# 07_-_CPU_CONNECTORS.net
KiCad netlist of a schematic drawn in Altium Designer
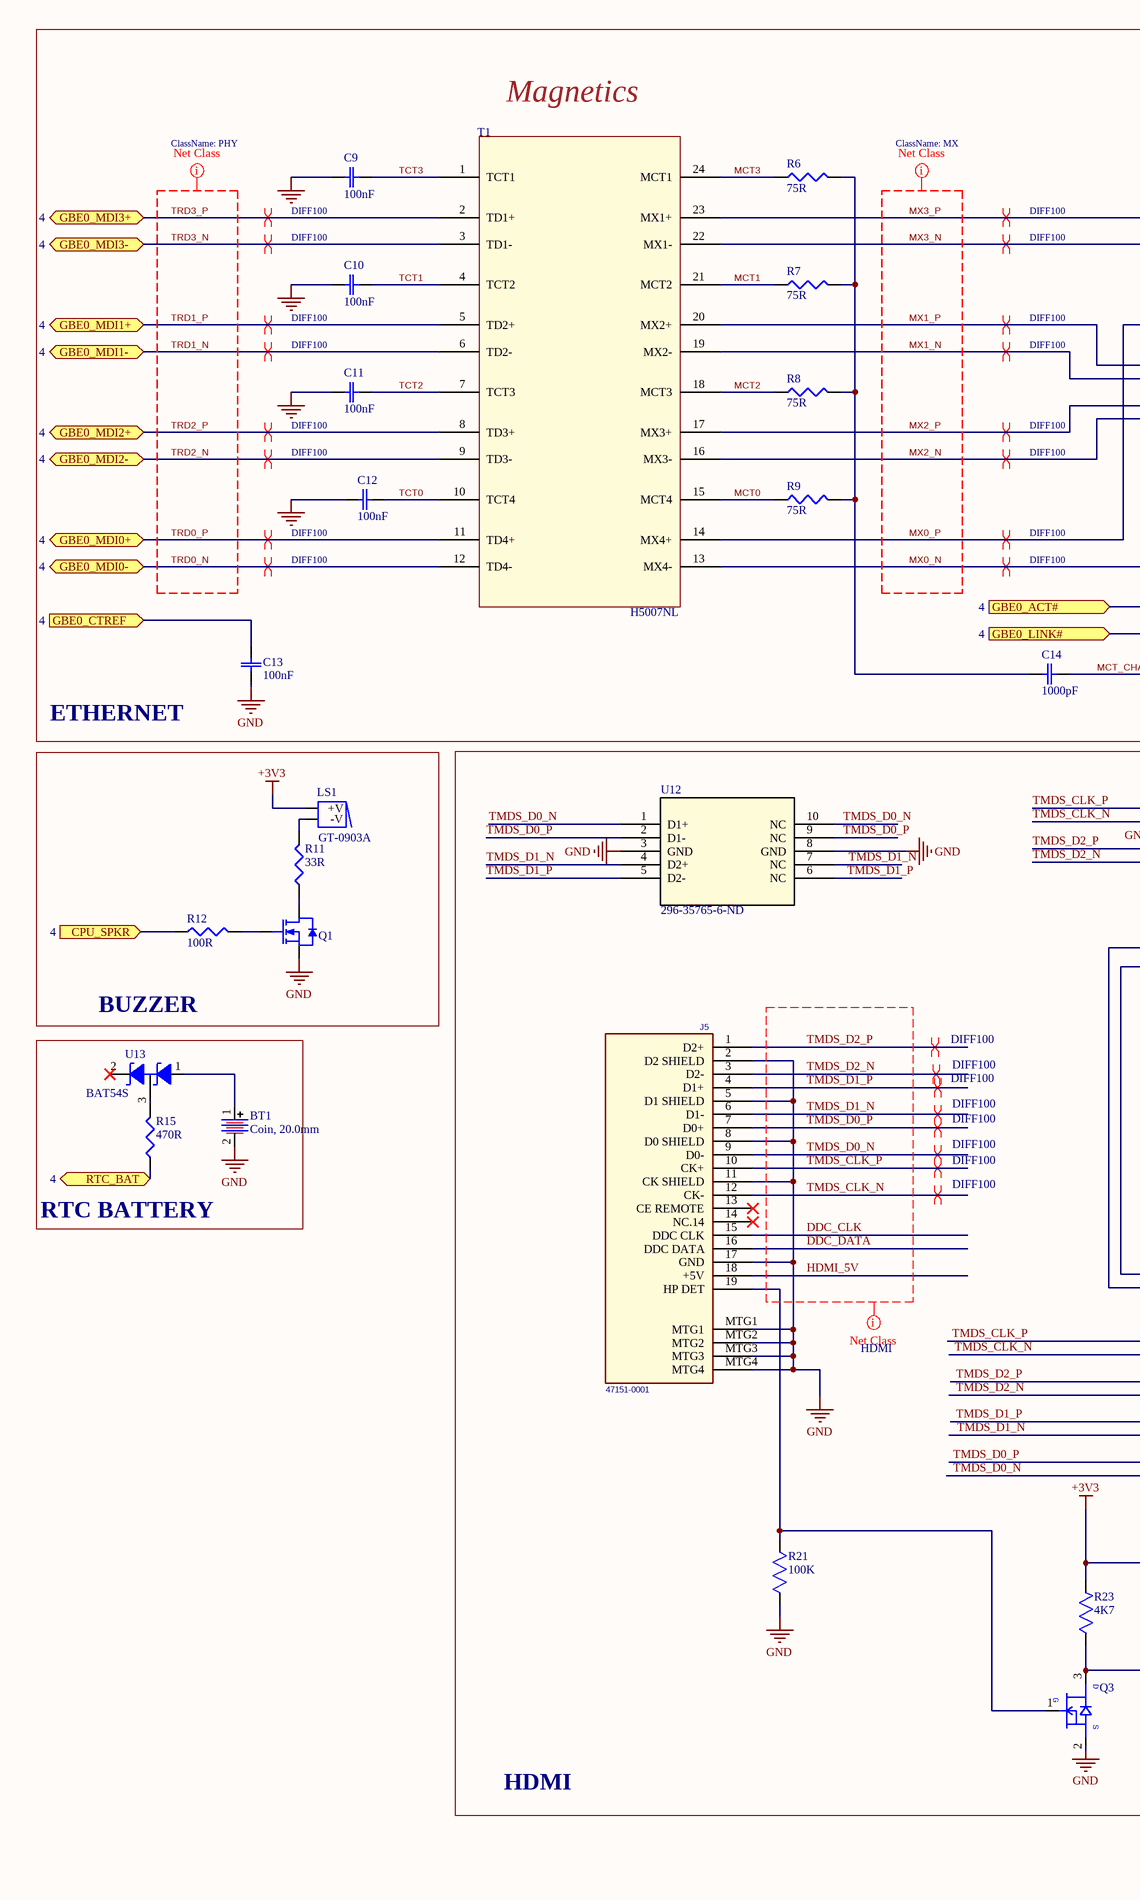
[diagram p0: [07] - CPU CONNECTORS .SchDoc, left]
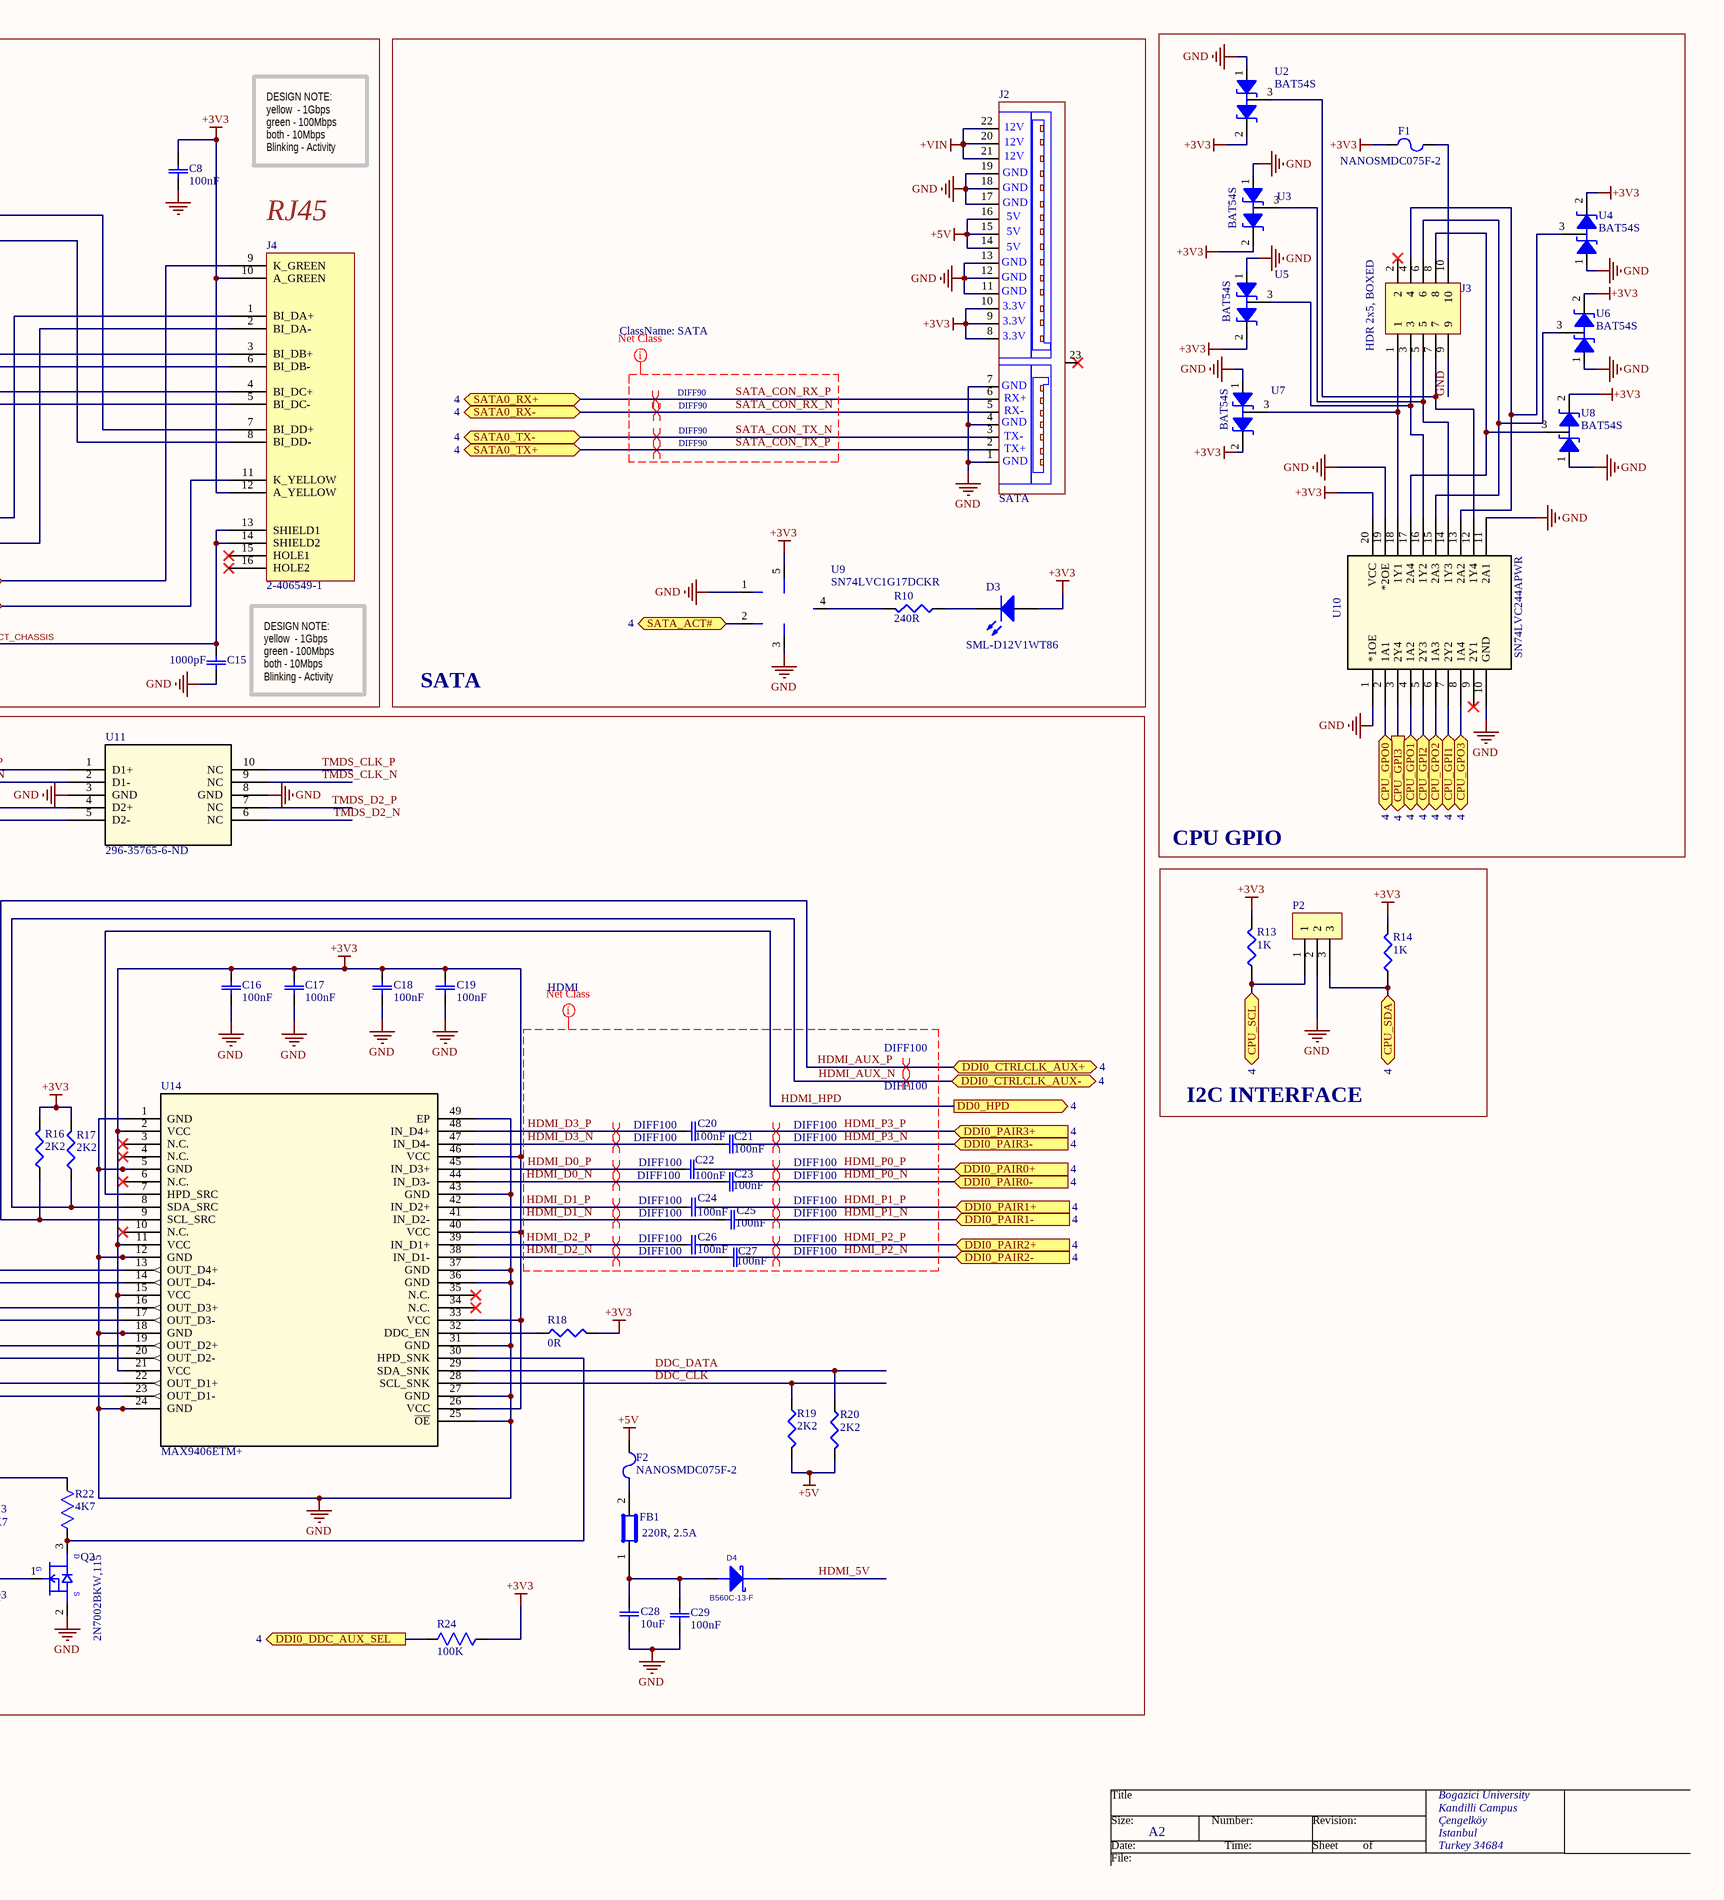
[diagram p1: [07] - CPU CONNECTORS .SchDoc, right]

(export (version "E")
  (design (tool "Eeschema 10.0.6"))
  (components
    (comp (ref "BT1")
      (value "Coin, 20.0mm")
      (footprint "BS-7")
      (description "BATTERY HOLDER COIN 20MM PC PIN")
      (fields
        (field (name "MANUFACTURER PART NUMBER") "BS-7")
        (field (name ".CHECKED SCH") "CHK")
        (field (name ".CHECKED PCB") "CHK")
      )
      (libsource (lib "SYNCBOX_V3I1") (part "CR2032"))
    )
    (comp (ref "C8")
      (value "100nF")
      (footprint "C0402")
      (description "CAP CER 0.1UF 50V X8R 0603")
      (fields (field (name "TOLERANCE") "±10%"))
      (libsource (lib "SYNCBOX_V3I1") (part "CL05A104KA5NNNC"))
    )
    (comp (ref "C9")
      (value "100nF")
      (footprint "C0402")
      (description "CAP CER 0.1UF 25V X5R 0402")
      (fields (field (name "TOLERANCE") "±10%") (field (name ".CHECKED SCH") "CHK"))
      (libsource (lib "SYNCBOX_V3I1") (part "CL05A104KA5NNNC"))
    )
    (comp (ref "C10")
      (value "100nF")
      (footprint "C0402")
      (description "CAP CER 0.1UF 25V X5R 0402")
      (fields (field (name "TOLERANCE") "±10%") (field (name ".CHECKED SCH") "CHK"))
      (libsource (lib "SYNCBOX_V3I1") (part "CL05A104KA5NNNC"))
    )
    (comp (ref "C11")
      (value "100nF")
      (footprint "C0402")
      (description "CAP CER 0.1UF 25V X5R 0402")
      (fields (field (name "TOLERANCE") "±10%") (field (name ".CHECKED SCH") "CHK"))
      (libsource (lib "SYNCBOX_V3I1") (part "CL05A104KA5NNNC"))
    )
    (comp (ref "C12")
      (value "100nF")
      (footprint "C0402")
      (description "CAP CER 0.1UF 25V X5R 0402")
      (fields (field (name "TOLERANCE") "±10%") (field (name ".CHECKED SCH") "CHK"))
      (libsource (lib "SYNCBOX_V3I1") (part "CL05A104KA5NNNC"))
    )
    (comp (ref "C13")
      (value "100nF")
      (footprint "C0402")
      (description "CAP CER 0.1UF 50V X8R 0603")
      (fields (field (name "TOLERANCE") "±10%"))
      (libsource (lib "SYNCBOX_V3I1") (part "CL05A104KA5NNNC"))
    )
    (comp (ref "C14")
      (value "1000pF")
      (footprint "C1206")
      (description "CAP CER 1206 1NF 2000V X7R 10% F")
      (fields (field (name "TOLERANCE") "±10%"))
      (libsource (lib "SYNCBOX_V3I1") (part "C1206X102KGRACAUTO"))
    )
    (comp (ref "C15")
      (value "1000pF")
      (footprint "C1206")
      (description "CAP CER 1206 1NF 2000V X7R 10% F")
      (fields (field (name "TOLERANCE") "±10%"))
      (libsource (lib "SYNCBOX_V3I1") (part "C1206X102KGRACAUTO"))
    )
    (comp (ref "C16")
      (value "100nF")
      (footprint "C0402")
      (description "CAP CER 0.1UF 25V X5R 0402")
      (fields (field (name "TOLERANCE") "±10%") (field (name ".CHECKED SCH") "CHK"))
      (libsource (lib "SYNCBOX_V3I1") (part "CL05A104KA5NNNC"))
    )
    (comp (ref "C17")
      (value "100nF")
      (footprint "C0402")
      (description "CAP CER 0.1UF 25V X5R 0402")
      (fields (field (name "TOLERANCE") "±10%") (field (name ".CHECKED SCH") "CHK"))
      (libsource (lib "SYNCBOX_V3I1") (part "CL05A104KA5NNNC"))
    )
    (comp (ref "C18")
      (value "100nF")
      (footprint "C0402")
      (description "CAP CER 0.1UF 25V X5R 0402")
      (fields (field (name "TOLERANCE") "±10%") (field (name ".CHECKED SCH") "CHK"))
      (libsource (lib "SYNCBOX_V3I1") (part "CL05A104KA5NNNC"))
    )
    (comp (ref "C19")
      (value "100nF")
      (footprint "C0402")
      (description "CAP CER 0.1UF 25V X5R 0402")
      (fields (field (name "TOLERANCE") "±10%") (field (name ".CHECKED SCH") "CHK"))
      (libsource (lib "SYNCBOX_V3I1") (part "CL05A104KA5NNNC"))
    )
    (comp (ref "C20")
      (value "100nF")
      (footprint "CAP_1608")
      (description "CAP CER 0.1UF 25V X5R 0402")
      (fields
        (field (name "MANUFACTURER_PART_NUMBER") "C1608X8R1H104K080AB")
        (field (name "TOLERANCE") "±10%")
        (field (name ".CHECKED SCH") "CHK")
      )
      (libsource (lib "SYNCBOX_V3I1") (part "C1608X8R1H104K08"))
    )
    (comp (ref "C21")
      (value "100nF")
      (footprint "CAP_1608")
      (description "CAP CER 0.1UF 25V X5R 0402")
      (fields
        (field (name "MANUFACTURER_PART_NUMBER") "C1608X8R1H104K080AB")
        (field (name "TOLERANCE") "±10%")
        (field (name ".CHECKED SCH") "CHK")
      )
      (libsource (lib "SYNCBOX_V3I1") (part "C1608X8R1H104K08"))
    )
    (comp (ref "C22")
      (value "100nF")
      (footprint "CAP_1608")
      (description "CAP CER 0.1UF 25V X5R 0402")
      (fields
        (field (name "MANUFACTURER_PART_NUMBER") "C1608X8R1H104K080AB")
        (field (name "TOLERANCE") "±10%")
        (field (name ".CHECKED SCH") "CHK")
      )
      (libsource (lib "SYNCBOX_V3I1") (part "C1608X8R1H104K08"))
    )
    (comp (ref "C23")
      (value "100nF")
      (footprint "CAP_1608")
      (description "CAP CER 0.1UF 25V X5R 0402")
      (fields
        (field (name "MANUFACTURER_PART_NUMBER") "C1608X8R1H104K080AB")
        (field (name "TOLERANCE") "±10%")
        (field (name ".CHECKED SCH") "CHK")
      )
      (libsource (lib "SYNCBOX_V3I1") (part "C1608X8R1H104K08"))
    )
    (comp (ref "C24")
      (value "100nF")
      (footprint "CAP_1608")
      (description "CAP CER 0.1UF 25V X5R 0402")
      (fields
        (field (name "MANUFACTURER_PART_NUMBER") "C1608X8R1H104K080AB")
        (field (name "TOLERANCE") "±10%")
        (field (name ".CHECKED SCH") "CHK")
      )
      (libsource (lib "SYNCBOX_V3I1") (part "C1608X8R1H104K08"))
    )
    (comp (ref "C25")
      (value "100nF")
      (footprint "CAP_1608")
      (description "CAP CER 0.1UF 25V X5R 0402")
      (fields
        (field (name "MANUFACTURER_PART_NUMBER") "C1608X8R1H104K080AB")
        (field (name "TOLERANCE") "±10%")
        (field (name ".CHECKED SCH") "CHK")
      )
      (libsource (lib "SYNCBOX_V3I1") (part "C1608X8R1H104K08"))
    )
    (comp (ref "C26")
      (value "100nF")
      (footprint "CAP_1608")
      (description "CAP CER 0.1UF 25V X5R 0402")
      (fields
        (field (name "MANUFACTURER_PART_NUMBER") "C1608X8R1H104K080AB")
        (field (name "TOLERANCE") "±10%")
        (field (name ".CHECKED SCH") "CHK")
      )
      (libsource (lib "SYNCBOX_V3I1") (part "C1608X8R1H104K08"))
    )
    (comp (ref "C27")
      (value "100nF")
      (footprint "CAP_1608")
      (description "CAP CER 0.1UF 25V X5R 0402")
      (fields
        (field (name "MANUFACTURER_PART_NUMBER") "C1608X8R1H104K080AB")
        (field (name "TOLERANCE") "±10%")
        (field (name ".CHECKED SCH") "CHK")
      )
      (libsource (lib "SYNCBOX_V3I1") (part "C1608X8R1H104K08"))
    )
    (comp (ref "C28")
      (value "10uF")
      (footprint "CAP_3216")
      (description "CAP CER 10UF 35V JB 1206")
      (fields
        (field (name "TOLERANCE") "±10%")
        (field (name "MANUFACTURER_PART_NUMBER") "C3216JB1V106K160AB")
        (field (name ".CHECKED SCH") "CHK")
      )
      (libsource (lib "SYNCBOX_V3I1") (part "C3216JB1V106K160"))
    )
    (comp (ref "C29")
      (value "100nF")
      (footprint "C0402")
      (description "CAP CER 0.1UF 50V X8R 0603")
      (fields (field (name "TOLERANCE") "±10%") (field (name ".CHECKED SCH") "CHK"))
      (libsource (lib "SYNCBOX_V3I1") (part "CL05A104KA5NNNC"))
    )
    (comp (ref "D3")
      (value "SML-D12V1WT86")
      (footprint "D0603_Directional")
      (description "LED RED DIFFUSED 1608 SMD")
      (fields (field (name ".CHECKED SCH") "CHK") (field (name ".CHECKED PCB") "CHK"))
      (libsource (lib "SYNCBOX_V3I1") (part "SML-D12V1WT86"))
    )
    (comp (ref "D4")
      (value "B560C-13-F")
      (footprint "SMC")
      (description "DIODE SCHOTTKY 60V 5A SMC")
      (fields (field (name "MANUFACTURER") "Diodes Inc") (field (name ".CHECKED SCH") "CHK"))
      (libsource (lib "SYNCBOX_V3I1") (part "B560C-13-F"))
    )
    (comp (ref "F1")
      (value "NANOSMDC075F-2")
      (footprint "FUS_NANO_TYCO")
      (description "PTC RESET FUSE 6V 750MA 1206")
      (libsource (lib "SYNCBOX_V3I1") (part "NANOSMDC075F-2"))
    )
    (comp (ref "F2")
      (value "NANOSMDC075F-2")
      (footprint "FUS_NANO_TYCO")
      (description "PTC RESET FUSE 6V 750MA 1206")
      (libsource (lib "SYNCBOX_V3I1") (part "NANOSMDC075F-2"))
    )
    (comp (ref "FB1")
      (value "220R, 2.5A")
      (footprint "C0603")
      (description "FERRITE CHIP 220 OHM 2500MA 0603")
      (fields
        (field (name "MANUFACTURER") "Murata Electronics North America")
        (field (name "MANUFACTURER PART NUMBER") "BLM18SG221TN1D")
        (field (name ".CHECKED SCH") "CHK")
      )
      (libsource (lib "SYNCBOX_V3I1") (part "BLM18SG221TN1D"))
    )
    (comp (ref "J2")
      (value "SATA")
      (footprint "SATA_Recepticle")
      (description "CONN SATA RECEPT 22POS SMD R/A")
      (libsource (lib "SYNCBOX_V3I1") (part "SATA"))
    )
    (comp (ref "J3")
      (value "HDR 2x5, BOXED")
      (footprint "HDR_2X5_2.54MM_BOXED")
      (description "CONN HEADER 10POS VERT 10GOLD")
      (fields
        (field (name "MANUFACTURER") "3M")
        (field (name "MANUFACTURER PART NUMBER") "D2510-6002-AR")
        (field (name ".CREATOR") "MM")
      )
      (libsource (lib "SYNCBOX_V3I1") (part "D2510-6002-AR"))
    )
    (comp (ref "J4")
      (value "2-406549-1")
      (footprint "RJ45LED")
      (description "CONN MOD JACK 8POS R/A G-Y PCB")
      (fields (field (name "MANUFACTURER") "Tyco"))
      (libsource (lib "SYNCBOX_V3I1") (part "2-406549-1"))
    )
    (comp (ref "J5")
      (value "47151-0001")
      (footprint "HDMI")
      (description "CONN RCPT 19POS HDMI RT ANG SMD")
      (fields (field (name "MANUFACTURER") "Molex Connector Corporation") (field (name ".CHECKED SCH") "CHK"))
      (libsource (lib "SYNCBOX_V3I1") (part "47151-0001"))
    )
    (comp (ref "LS1")
      (value "GT-0903A")
      (footprint "GT-0903A")
      (description "AUDIO MAGNETIC XDCR 2-4V TH")
      (libsource (lib "SYNCBOX_V3I1") (part "GT-0903A"))
    )
    (comp (ref "P2")
      (value "76384-303LF")
      (footprint "HDR_1x3_2.54MM_SHDR_V2")
      (description "CONN HEADER 3POS .100\" STR GOLD")
      (fields
        (field (name "MANUFACTURER") "FCI")
        (field (name ".CREATOR") "MM")
        (field (name ".CHECKED PCB") "CHK")
        (field (name ".CHECKED SCH") "CHK")
      )
      (libsource (lib "SYNCBOX_V3I1") (part "76384-303LF"))
    )
    (comp (ref "Q1")
      (value "MOSFET N-CH 20V 1A SOT323")
      (footprint "SC70_SOT323")
      (fields (field (name "PUBLISHER") "Altium Limited"))
      (libsource (lib "SYNCBOX_V3I1") (part "DMG1012UW-7"))
    )
    (comp (ref "Q2")
      (value "2N7002BKW,115")
      (footprint "SC70_SOT323")
      (description "MOSFET N-CH 60V 310MA SOT323")
      (fields (field (name "MANUFACTURER") "NXP Semiconductors") (field (name ".CHECKED SCH") "CHK"))
      (libsource (lib "SYNCBOX_V3I1") (part "2N7002BKW,115"))
    )
    (comp (ref "Q3")
      (value "2N7002BKW,115")
      (footprint "SC70_SOT323")
      (description "MOSFET N-CH 60V 310MA SOT323")
      (fields (field (name "MANUFACTURER") "NXP Semiconductors") (field (name ".CHECKED SCH") "CHK"))
      (libsource (lib "SYNCBOX_V3I1") (part "2N7002BKW,115"))
    )
    (comp (ref "R6")
      (value "75R")
      (footprint "R0402")
      (description "RES SMD 75 OHM 1% 1/16W 0402")
      (fields (field (name "TOLERANCE") "±1%"))
      (libsource (lib "SYNCBOX_V3I1") (part "RC1005F750CS"))
    )
    (comp (ref "R7")
      (value "75R")
      (footprint "R0402")
      (description "RES SMD 75 OHM 1% 1/16W 0402")
      (fields (field (name "TOLERANCE") "±1%"))
      (libsource (lib "SYNCBOX_V3I1") (part "RC1005F750CS"))
    )
    (comp (ref "R8")
      (value "75R")
      (footprint "R0402")
      (description "RES SMD 75 OHM 1% 1/16W 0402")
      (fields (field (name "TOLERANCE") "±1%"))
      (libsource (lib "SYNCBOX_V3I1") (part "RC1005F750CS"))
    )
    (comp (ref "R9")
      (value "75R")
      (footprint "R0402")
      (description "RES SMD 75 OHM 1% 1/16W 0402")
      (fields (field (name "TOLERANCE") "±1%"))
      (libsource (lib "SYNCBOX_V3I1") (part "RC1005F750CS"))
    )
    (comp (ref "R10")
      (value "240R")
      (footprint "R0402")
      (description "RES TF 240 OHM 1% 0.0625W 0402")
      (fields
        (field (name "MANUFACTURER") "Stackpole Electronics Inc")
        (field (name "MANUFACTURER PART NUMBER") "RMCF0402FT240R")
      )
      (libsource (lib "SYNCBOX_V3I1") (part "RMCF0402FT240R"))
    )
    (comp (ref "R11")
      (value "33R")
      (footprint "R0402")
      (description "RES SMD 33 OHM 1% 1/10W 0402")
      (fields (field (name "TOLERANCE") "±1%") (field (name ".CHECKED SCH") "CHK"))
      (libsource (lib "SYNCBOX_V3I1") (part "ERJ-2RKF33R0X"))
    )
    (comp (ref "R12")
      (value "100R")
      (footprint "R0402")
      (description "RES SMD 100 OHM 5% 1/16W 0402")
      (fields (field (name "TOLERANCE") "5 %"))
      (libsource (lib "SYNCBOX_V3I1") (part "RC0402JR-07100RL"))
    )
    (comp (ref "R13")
      (value "1K")
      (footprint "R0402")
      (description "RES SMD 1K OHM 1% 1/10W 0402")
      (fields (field (name "TOLERANCE") "±1%"))
      (libsource (lib "SYNCBOX_V3I1") (part "ERJ-2RKF1001X"))
    )
    (comp (ref "R14")
      (value "1K")
      (footprint "R0402")
      (description "RES SMD 1K OHM 1% 1/10W 0402")
      (fields (field (name "TOLERANCE") "±1%"))
      (libsource (lib "SYNCBOX_V3I1") (part "ERJ-2RKF1001X"))
    )
    (comp (ref "R15")
      (value "470R")
      (footprint "R0402")
      (description "RES 470 OHM 1/16W 5% 0402 SMD")
      (fields (field (name "MANUFACTURER PART NUMBER") "CRGCQ0402J470R") (field (name ".CHECKED SCH") "CHK"))
      (libsource (lib "SYNCBOX_V3I1") (part "CRGCQ0402J470R"))
    )
    (comp (ref "R16")
      (value "2K2")
      (footprint "R0402")
      (description "RES SMD 2.2K OHM 1% 1/16W 0402")
      (fields (field (name "TOLERANCE") "±1%"))
      (libsource (lib "SYNCBOX_V3I1") (part "RC1005F222CS"))
    )
    (comp (ref "R17")
      (value "2K2")
      (footprint "R0402")
      (description "RES SMD 2.2K OHM 1% 1/16W 0402")
      (fields (field (name "TOLERANCE") "±1%"))
      (libsource (lib "SYNCBOX_V3I1") (part "RC1005F222CS"))
    )
    (comp (ref "R18")
      (value "0R")
      (footprint "R0402")
      (description "RES SMD 0 OHM JUMPER 1/16W 0402")
      (fields (field (name "TOLERANCE") "Jumper") (field (name ".CHECKED SCH") "CHK"))
      (libsource (lib "SYNCBOX_V3I1") (part "RC1005J000CS"))
    )
    (comp (ref "R19")
      (value "2K2")
      (footprint "R0402")
      (description "RES SMD 2.2K OHM 1% 1/16W 0402")
      (fields (field (name "TOLERANCE") "±1%") (field (name ".CHECKED SCH") "CHK"))
      (libsource (lib "SYNCBOX_V3I1") (part "RC1005F222CS"))
    )
    (comp (ref "R20")
      (value "2K2")
      (footprint "R0402")
      (description "RES SMD 2.2K OHM 1% 1/16W 0402")
      (fields (field (name "TOLERANCE") "±1%") (field (name ".CHECKED SCH") "CHK"))
      (libsource (lib "SYNCBOX_V3I1") (part "RC1005F222CS"))
    )
    (comp (ref "R21")
      (value "100K")
      (footprint "STA_RNCP0805-M")
      (description "RES SMD 100K OHM 1% 1/8W 0805")
      (fields (field (name "TOLERANCE") "±1%") (field (name ".CHECKED SCH") "CHK"))
      (libsource (lib "SYNCBOX_V3I1") (part "RC2012F104CS"))
    )
    (comp (ref "R22")
      (value "4K7")
      (footprint "RES0805_CRG_TYCO")
      (description "RES SMD 4.7K OHM 1% 1/8W 0805")
      (fields
        (field (name "MANUFACTURER_PART_NUMBER") "CRG0805F4K7")
        (field (name "TOLERANCE") "±1%")
        (field (name ".CHECKED SCH") "CHK")
      )
      (libsource (lib "SYNCBOX_V3I1") (part "CRG0805F4K7"))
    )
    (comp (ref "R23")
      (value "4K7")
      (footprint "RES0805_CRG_TYCO")
      (description "RES SMD 4.7K OHM 1% 1/8W 0805")
      (fields
        (field (name "MANUFACTURER_PART_NUMBER") "CRG0805F4K7")
        (field (name "TOLERANCE") "±1%")
        (field (name ".CHECKED SCH") "CHK")
      )
      (libsource (lib "SYNCBOX_V3I1") (part "CRG0805F4K7"))
    )
    (comp (ref "R24")
      (value "100K")
      (footprint "STA_RNCP0805-M")
      (description "RES SMD 100K OHM 1% 1/8W 0805")
      (fields (field (name "TOLERANCE") "±1%") (field (name ".CHECKED SCH") "CHK"))
      (libsource (lib "SYNCBOX_V3I1") (part "RC2012F104CS"))
    )
    (comp (ref "T1")
      (value "H5007NL")
      (footprint "H5007NL")
      (description "MODULE SINGLE GIGABIT LAN 24SOIC")
      (fields (field (name "MANUFACTURER") "PULSE ELECTRONICS CORPORATION"))
      (libsource (lib "SYNCBOX_V3I1") (part "H5007NL"))
    )
    (comp (ref "U2")
      (value "BAT54S")
      (footprint "SOT-23")
      (description "DIODE ARRAY SCHOTTKY 30V SOT23")
      (libsource (lib "SYNCBOX_V3I1") (part "BAT54S"))
    )
    (comp (ref "U3")
      (value "BAT54S")
      (footprint "SOT-23")
      (description "DIODE ARRAY SCHOTTKY 30V SOT23")
      (libsource (lib "SYNCBOX_V3I1") (part "BAT54S"))
    )
    (comp (ref "U4")
      (value "BAT54S")
      (footprint "SOT-23")
      (description "DIODE ARRAY SCHOTTKY 30V SOT23")
      (libsource (lib "SYNCBOX_V3I1") (part "BAT54S"))
    )
    (comp (ref "U5")
      (value "BAT54S")
      (footprint "SOT-23")
      (description "DIODE ARRAY SCHOTTKY 30V SOT23")
      (libsource (lib "SYNCBOX_V3I1") (part "BAT54S"))
    )
    (comp (ref "U6")
      (value "BAT54S")
      (footprint "SOT-23")
      (description "DIODE ARRAY SCHOTTKY 30V SOT23")
      (libsource (lib "SYNCBOX_V3I1") (part "BAT54S"))
    )
    (comp (ref "U7")
      (value "BAT54S")
      (footprint "SOT-23")
      (description "DIODE ARRAY SCHOTTKY 30V SOT23")
      (libsource (lib "SYNCBOX_V3I1") (part "BAT54S"))
    )
    (comp (ref "U8")
      (value "BAT54S")
      (footprint "SOT-23")
      (description "DIODE ARRAY SCHOTTKY 30V SOT23")
      (libsource (lib "SYNCBOX_V3I1") (part "BAT54S"))
    )
    (comp (ref "U9")
      (value "SN74LVC1G17DCKR")
      (footprint "DCK5")
      (fields (field (name "MANUFACTURER") "Texas Instruments") (field (name "BASE PART NUMBER") "74LVC1G17"))
      (libsource (lib "SYNCBOX_V3I1") (part "SN74LVC1G17DCKR"))
    )
    (comp (ref "U10")
      (value "SN74LVC244APWR")
      (footprint "PW20")
      (description "IC BUF NON-INVERT 3.6V 20TSSOP")
      (fields (field (name "MANUFACTURER") "Texas Instruments") (field (name "BASE PART NUMBER") "74LVC244"))
      (libsource (lib "SYNCBOX_V3I1") (part "SN74LVC244APWR"))
    )
    (comp (ref "U11")
      (value "296-35765-6-ND")
      (footprint "DQA10")
      (description "TVS DIODE 5.5V 14V 10SON")
      (fields
        (field (name "MANUFACTURER_PART_NUMBER") "TPD4E05U06DQAR")
        (field (name "BASE PART NUMBER") "TPD4E05U06")
        (field (name ".CHECKED SCH") "CHK")
      )
      (libsource (lib "SYNCBOX_V3I1") (part "TPD4E05U06DQAR"))
    )
    (comp (ref "U12")
      (value "296-35765-6-ND")
      (footprint "DQA10")
      (description "TVS DIODE 5.5V 14V 10SON")
      (fields
        (field (name "MANUFACTURER_PART_NUMBER") "TPD4E05U06DQAR")
        (field (name "BASE PART NUMBER") "TPD4E05U06")
        (field (name ".CHECKED SCH") "CHK")
      )
      (libsource (lib "SYNCBOX_V3I1") (part "TPD4E05U06DQAR"))
    )
    (comp (ref "U13")
      (value "BAT54S")
      (footprint "SOT-23")
      (description "DIODE ARRAY SCHOTTKY 30V SOT23")
      (libsource (lib "SYNCBOX_V3I1") (part "BAT54S"))
    )
    (comp (ref "U14")
      (value "MAX9406ETM+")
      (footprint "21-0144H_T4877-6")
      (description "IC DVI/HDMI LVL SHIFTR 48TQFN")
      (fields (field (name "BASE PART NUMBER") "MAX9406") (field (name ".CHECKED SCH") "CHK"))
      (libsource (lib "SYNCBOX_V3I1") (part "MAX9406ETM+"))
    )
  )
  (nets
    (net (code "1") (name "+3V3") (class "Default")
      (node (ref "C16") (pin "2") (pinfunction "2_2") (pintype "passive"))
      (node (ref "C17") (pin "2") (pinfunction "2_2") (pintype "passive"))
      (node (ref "C18") (pin "2") (pinfunction "2_2") (pintype "passive"))
      (node (ref "C19") (pin "2") (pinfunction "2_2") (pintype "passive"))
      (node (ref "C8") (pin "2") (pinfunction "2_2") (pintype "passive"))
      (node (ref "D3") (pin "1") (pinfunction "A_1") (pintype "passive"))
      (node (ref "F1") (pin "2") (pinfunction "2_2") (pintype "passive"))
      (node (ref "J2") (pin "10") (pinfunction "10_10") (pintype "passive"))
      (node (ref "J2") (pin "8") (pinfunction "8_8") (pintype "passive"))
      (node (ref "J2") (pin "9") (pinfunction "9_9") (pintype "passive"))
      (node (ref "J4") (pin "10") (pinfunction "A_GREEN_10") (pintype "passive"))
      (node (ref "J4") (pin "12") (pinfunction "A_YELLOW_12") (pintype "passive"))
      (node (ref "LS1") (pin "1") (pinfunction "+V_1") (pintype "passive"))
      (node (ref "R13") (pin "2") (pinfunction "2_2") (pintype "passive"))
      (node (ref "R14") (pin "2") (pinfunction "2_2") (pintype "passive"))
      (node (ref "R16") (pin "2") (pinfunction "2_2") (pintype "passive"))
      (node (ref "R17") (pin "2") (pinfunction "2_2") (pintype "passive"))
      (node (ref "R18") (pin "2") (pinfunction "2_2") (pintype "passive"))
      (node (ref "R22") (pin "1") (pinfunction "1_1") (pintype "passive"))
      (node (ref "R23") (pin "1") (pinfunction "1_1") (pintype "passive"))
      (node (ref "R24") (pin "1") (pinfunction "1_1") (pintype "passive"))
      (node (ref "U10") (pin "20") (pinfunction "VCC_20") (pintype "power_in"))
      (node (ref "U14") (pin "11") (pinfunction "VCC_11") (pintype "power_in"))
      (node (ref "U14") (pin "15") (pinfunction "VCC_15") (pintype "power_in"))
      (node (ref "U14") (pin "2") (pinfunction "VCC_2") (pintype "power_in"))
      (node (ref "U14") (pin "21") (pinfunction "VCC_21") (pintype "passive"))
      (node (ref "U14") (pin "26") (pinfunction "VCC_26") (pintype "power_in"))
      (node (ref "U14") (pin "33") (pinfunction "VCC_33") (pintype "power_in"))
      (node (ref "U14") (pin "40") (pinfunction "VCC_40") (pintype "power_in"))
      (node (ref "U14") (pin "46") (pinfunction "VCC_46") (pintype "power_in"))
      (node (ref "U2") (pin "2") (pinfunction "2_2") (pintype "passive"))
      (node (ref "U3") (pin "2") (pinfunction "2_2") (pintype "passive"))
      (node (ref "U4") (pin "2") (pinfunction "2_2") (pintype "passive"))
      (node (ref "U5") (pin "2") (pinfunction "2_2") (pintype "passive"))
      (node (ref "U6") (pin "2") (pinfunction "2_2") (pintype "passive"))
      (node (ref "U7") (pin "2") (pinfunction "2_2") (pintype "passive"))
      (node (ref "U8") (pin "2") (pinfunction "2_2") (pintype "passive"))
      (node (ref "U9") (pin "5") (pinfunction "VCC_5") (pintype "passive"))
    )
    (net (code "2") (name "+5V") (class "Default")
      (node (ref "F2") (pin "2") (pinfunction "2_2") (pintype "passive"))
      (node (ref "J2") (pin "14") (pinfunction "14_14") (pintype "passive"))
      (node (ref "J2") (pin "15") (pinfunction "15_15") (pintype "passive"))
      (node (ref "J2") (pin "16") (pinfunction "16_16") (pintype "passive"))
      (node (ref "R19") (pin "2") (pinfunction "2_2") (pintype "passive"))
      (node (ref "R20") (pin "2") (pinfunction "2_2") (pintype "passive"))
    )
    (net (code "3") (name "+VIN") (class "Default")
      (node (ref "J2") (pin "20") (pinfunction "20_20") (pintype "passive"))
      (node (ref "J2") (pin "21") (pinfunction "21_21") (pintype "passive"))
      (node (ref "J2") (pin "22") (pinfunction "22_22") (pintype "passive"))
    )
    (net (code "4") (name "/CPU_GPI1") (class "Default")
      (node (ref "U10") (pin "7") (pinfunction "2Y2_7") (pintype "passive"))
    )
    (net (code "5") (name "/CPU_GPI2") (class "Default")
      (node (ref "U10") (pin "5") (pinfunction "2Y3_5") (pintype "passive"))
    )
    (net (code "6") (name "/CPU_GPI3") (class "Default")
      (node (ref "U10") (pin "3") (pinfunction "2Y4_3") (pintype "passive"))
    )
    (net (code "7") (name "/CPU_GPO0") (class "Default")
      (node (ref "U10") (pin "2") (pinfunction "1A1_2") (pintype "passive"))
    )
    (net (code "8") (name "/CPU_GPO1") (class "Default")
      (node (ref "U10") (pin "4") (pinfunction "1A2_4") (pintype "passive"))
    )
    (net (code "9") (name "/CPU_GPO2") (class "Default")
      (node (ref "U10") (pin "6") (pinfunction "1A3_6") (pintype "passive"))
    )
    (net (code "10") (name "/CPU_GPO3") (class "Default")
      (node (ref "U10") (pin "8") (pinfunction "1A4_8") (pintype "passive"))
    )
    (net (code "11") (name "/CPU_SCL") (class "Default")
      (node (ref "P2") (pin "1") (pinfunction "1_1") (pintype "passive"))
      (node (ref "R13") (pin "1") (pinfunction "1_1") (pintype "passive"))
    )
    (net (code "12") (name "/CPU_SDA") (class "Default")
      (node (ref "P2") (pin "3") (pinfunction "3_3") (pintype "passive"))
      (node (ref "R14") (pin "1") (pinfunction "1_1") (pintype "passive"))
    )
    (net (code "13") (name "/CPU_SPKR") (class "Default")
      (node (ref "R12") (pin "1") (pinfunction "1_1") (pintype "passive"))
    )
    (net (code "14") (name "/DDC_CLK") (class "Default")
      (node (ref "J5") (pin "15") (pinfunction "DDC_CLK_15") (pintype "passive"))
      (node (ref "R19") (pin "1") (pinfunction "1_1") (pintype "passive"))
      (node (ref "U14") (pin "28") (pinfunction "SCL_SNK_28") (pintype "passive"))
    )
    (net (code "15") (name "/DDC_DATA") (class "Default")
      (node (ref "J5") (pin "16") (pinfunction "DDC_DATA_16") (pintype "passive"))
      (node (ref "R20") (pin "1") (pinfunction "1_1") (pintype "passive"))
      (node (ref "U14") (pin "29") (pinfunction "SDA_SNK_29") (pintype "passive"))
    )
    (net (code "16") (name "/DDI0_DDC_AUX_SEL") (class "Default")
      (node (ref "R24") (pin "2") (pinfunction "2_2") (pintype "passive"))
    )
    (net (code "17") (name "/GBE0_ACT#") (class "Default")
      (node (ref "J4") (pin "9") (pinfunction "K_GREEN_9") (pintype "passive"))
    )
    (net (code "18") (name "/GBE0_CTREF") (class "Default")
      (node (ref "C13") (pin "2") (pinfunction "2_2") (pintype "passive"))
    )
    (net (code "19") (name "/GBE0_LINK#") (class "Default")
      (node (ref "J4") (pin "11") (pinfunction "K_YELLOW_11") (pintype "passive"))
    )
    (net (code "20") (name "/HDMI_5V") (class "Default")
      (node (ref "D4") (pin "1") (pinfunction "cathode_1") (pintype "passive"))
      (node (ref "J5") (pin "18") (pinfunction "+5V_18") (pintype "passive"))
    )
    (net (code "21") (name "/HDMI_AUX_N") (class "Default")
      (node (ref "R17") (pin "1") (pinfunction "1_1") (pintype "passive"))
      (node (ref "U14") (pin "8") (pinfunction "SDA_SRC_8") (pintype "passive"))
    )
    (net (code "22") (name "/HDMI_AUX_P") (class "Default")
      (node (ref "R16") (pin "1") (pinfunction "1_1") (pintype "passive"))
      (node (ref "U14") (pin "9") (pinfunction "SCL_SRC_9") (pintype "passive"))
    )
    (net (code "23") (name "/HDMI_D0_N") (class "Default")
      (node (ref "C23") (pin "1") (pinfunction "1_1") (pintype "passive"))
      (node (ref "U14") (pin "44") (pinfunction "IN_D3-_44") (pintype "passive"))
    )
    (net (code "24") (name "/HDMI_D0_P") (class "Default")
      (node (ref "C22") (pin "1") (pinfunction "1_1") (pintype "passive"))
      (node (ref "U14") (pin "45") (pinfunction "IN_D3+_45") (pintype "passive"))
    )
    (net (code "25") (name "/HDMI_D1_N") (class "Default")
      (node (ref "C25") (pin "1") (pinfunction "1_1") (pintype "passive"))
      (node (ref "U14") (pin "41") (pinfunction "IN_D2-_41") (pintype "passive"))
    )
    (net (code "26") (name "/HDMI_D1_P") (class "Default")
      (node (ref "C24") (pin "1") (pinfunction "1_1") (pintype "passive"))
      (node (ref "U14") (pin "42") (pinfunction "IN_D2+_42") (pintype "passive"))
    )
    (net (code "27") (name "/HDMI_D2_N") (class "Default")
      (node (ref "C27") (pin "1") (pinfunction "1_1") (pintype "passive"))
      (node (ref "U14") (pin "38") (pinfunction "IN_D1-_38") (pintype "passive"))
    )
    (net (code "28") (name "/HDMI_D2_P") (class "Default")
      (node (ref "C26") (pin "1") (pinfunction "1_1") (pintype "passive"))
      (node (ref "U14") (pin "39") (pinfunction "IN_D1+_39") (pintype "passive"))
    )
    (net (code "29") (name "/HDMI_D3_N") (class "Default")
      (node (ref "C21") (pin "1") (pinfunction "1_1") (pintype "passive"))
      (node (ref "U14") (pin "47") (pinfunction "IN_D4-_47") (pintype "passive"))
    )
    (net (code "30") (name "/HDMI_D3_P") (class "Default")
      (node (ref "C20") (pin "1") (pinfunction "1_1") (pintype "passive"))
      (node (ref "U14") (pin "48") (pinfunction "IN_D4+_48") (pintype "passive"))
    )
    (net (code "31") (name "/HDMI_HPD") (class "Default")
      (node (ref "U14") (pin "7") (pinfunction "HPD_SRC_7") (pintype "passive"))
    )
    (net (code "32") (name "/HDMI_P0_N") (class "Default")
      (node (ref "C23") (pin "2") (pinfunction "2_2") (pintype "passive"))
    )
    (net (code "33") (name "/HDMI_P0_P") (class "Default")
      (node (ref "C22") (pin "2") (pinfunction "2_2") (pintype "passive"))
    )
    (net (code "34") (name "/HDMI_P1_N") (class "Default")
      (node (ref "C25") (pin "2") (pinfunction "2_2") (pintype "passive"))
    )
    (net (code "35") (name "/HDMI_P1_P") (class "Default")
      (node (ref "C24") (pin "2") (pinfunction "2_2") (pintype "passive"))
    )
    (net (code "36") (name "/HDMI_P2_N") (class "Default")
      (node (ref "C27") (pin "2") (pinfunction "2_2") (pintype "passive"))
    )
    (net (code "37") (name "/HDMI_P2_P") (class "Default")
      (node (ref "C26") (pin "2") (pinfunction "2_2") (pintype "passive"))
    )
    (net (code "38") (name "/HDMI_P3_N") (class "Default")
      (node (ref "C21") (pin "2") (pinfunction "2_2") (pintype "passive"))
    )
    (net (code "39") (name "/HDMI_P3_P") (class "Default")
      (node (ref "C20") (pin "2") (pinfunction "2_2") (pintype "passive"))
    )
    (net (code "40") (name "/MCT0") (class "Default")
      (node (ref "R9") (pin "1") (pinfunction "1_1") (pintype "passive"))
      (node (ref "T1") (pin "15") (pinfunction "MCT4_15") (pintype "passive"))
    )
    (net (code "41") (name "/MCT1") (class "Default")
      (node (ref "R7") (pin "1") (pinfunction "1_1") (pintype "passive"))
      (node (ref "T1") (pin "21") (pinfunction "MCT2_21") (pintype "passive"))
    )
    (net (code "42") (name "/MCT2") (class "Default")
      (node (ref "R8") (pin "1") (pinfunction "1_1") (pintype "passive"))
      (node (ref "T1") (pin "18") (pinfunction "MCT3_18") (pintype "passive"))
    )
    (net (code "43") (name "/MCT3") (class "Default")
      (node (ref "R6") (pin "1") (pinfunction "1_1") (pintype "passive"))
      (node (ref "T1") (pin "24") (pinfunction "MCT1_24") (pintype "passive"))
    )
    (net (code "44") (name "/MCT_CHASSIS") (class "Default")
      (node (ref "C14") (pin "1") (pinfunction "1_1") (pintype "passive"))
      (node (ref "C15") (pin "1") (pinfunction "1_1") (pintype "passive"))
      (node (ref "J4") (pin "13") (pinfunction "SHIELD1_13") (pintype "passive"))
      (node (ref "J4") (pin "14") (pinfunction "SHIELD2_14") (pintype "passive"))
    )
    (net (code "45") (name "/MX0_N") (class "Default")
      (node (ref "J4") (pin "2") (pinfunction "BI_DA-_2") (pintype "passive"))
      (node (ref "T1") (pin "13") (pinfunction "MX4-_13") (pintype "passive"))
    )
    (net (code "46") (name "/MX0_P") (class "Default")
      (node (ref "J4") (pin "1") (pinfunction "BI_DA+_1") (pintype "passive"))
      (node (ref "T1") (pin "14") (pinfunction "MX4+_14") (pintype "passive"))
    )
    (net (code "47") (name "/MX1_N") (class "Default")
      (node (ref "J4") (pin "6") (pinfunction "BI_DB-_6") (pintype "passive"))
      (node (ref "T1") (pin "19") (pinfunction "MX2-_19") (pintype "passive"))
    )
    (net (code "48") (name "/MX1_P") (class "Default")
      (node (ref "J4") (pin "3") (pinfunction "BI_DB+_3") (pintype "passive"))
      (node (ref "T1") (pin "20") (pinfunction "MX2+_20") (pintype "passive"))
    )
    (net (code "49") (name "/MX2_N") (class "Default")
      (node (ref "J4") (pin "5") (pinfunction "BI_DC-_5") (pintype "passive"))
      (node (ref "T1") (pin "16") (pinfunction "MX3-_16") (pintype "passive"))
    )
    (net (code "50") (name "/MX2_P") (class "Default")
      (node (ref "J4") (pin "4") (pinfunction "BI_DC+_4") (pintype "passive"))
      (node (ref "T1") (pin "17") (pinfunction "MX3+_17") (pintype "passive"))
    )
    (net (code "51") (name "/MX3_N") (class "Default")
      (node (ref "J4") (pin "8") (pinfunction "BI_DD-_8") (pintype "passive"))
      (node (ref "T1") (pin "22") (pinfunction "MX1-_22") (pintype "passive"))
    )
    (net (code "52") (name "/MX3_P") (class "Default")
      (node (ref "J4") (pin "7") (pinfunction "BI_DD+_7") (pintype "passive"))
      (node (ref "T1") (pin "23") (pinfunction "MX1+_23") (pintype "passive"))
    )
    (net (code "53") (name "/RTC_BAT") (class "Default")
      (node (ref "R15") (pin "1") (pinfunction "1_1") (pintype "passive"))
    )
    (net (code "54") (name "/SATA_ACT#") (class "Default")
      (node (ref "U9") (pin "2") (pinfunction "A_2") (pintype "passive"))
    )
    (net (code "55") (name "/SATA_CON_RX_N") (class "Default")
      (node (ref "J2") (pin "5") (pinfunction "5_5") (pintype "passive"))
    )
    (net (code "56") (name "/SATA_CON_RX_P") (class "Default")
      (node (ref "J2") (pin "6") (pinfunction "6_6") (pintype "passive"))
    )
    (net (code "57") (name "/SATA_CON_TX_N") (class "Default")
      (node (ref "J2") (pin "3") (pinfunction "3_3") (pintype "passive"))
    )
    (net (code "58") (name "/SATA_CON_TX_P") (class "Default")
      (node (ref "J2") (pin "2") (pinfunction "2_2") (pintype "passive"))
    )
    (net (code "59") (name "/TCT0") (class "Default")
      (node (ref "C12") (pin "2") (pinfunction "2_2") (pintype "passive"))
      (node (ref "T1") (pin "10") (pinfunction "TCT4_10") (pintype "passive"))
    )
    (net (code "60") (name "/TCT1") (class "Default")
      (node (ref "C10") (pin "2") (pinfunction "2_2") (pintype "passive"))
      (node (ref "T1") (pin "4") (pinfunction "TCT2_4") (pintype "passive"))
    )
    (net (code "61") (name "/TCT2") (class "Default")
      (node (ref "C11") (pin "2") (pinfunction "2_2") (pintype "passive"))
      (node (ref "T1") (pin "7") (pinfunction "TCT3_7") (pintype "passive"))
    )
    (net (code "62") (name "/TCT3") (class "Default")
      (node (ref "C9") (pin "2") (pinfunction "2_2") (pintype "passive"))
      (node (ref "T1") (pin "1") (pinfunction "TCT1_1") (pintype "passive"))
    )
    (net (code "63") (name "/TMDS_CLK_N") (class "Default")
      (node (ref "J5") (pin "12") (pinfunction "CK-_12") (pintype "passive"))
      (node (ref "U11") (pin "2") (pinfunction "D1-_2") (pintype "passive"))
      (node (ref "U11") (pin "9") (pinfunction "NC_9") (pintype "passive"))
      (node (ref "U14") (pin "14") (pinfunction "OUT_D4-_14") (pintype "output"))
    )
    (net (code "64") (name "/TMDS_CLK_P") (class "Default")
      (node (ref "J5") (pin "10") (pinfunction "CK+_10") (pintype "passive"))
      (node (ref "U11") (pin "1") (pinfunction "D1+_1") (pintype "passive"))
      (node (ref "U11") (pin "10") (pinfunction "NC_10") (pintype "passive"))
      (node (ref "U14") (pin "13") (pinfunction "OUT_D4+_13") (pintype "output"))
    )
    (net (code "65") (name "/TMDS_D0_N") (class "Default")
      (node (ref "J5") (pin "9") (pinfunction "D0-_9") (pintype "passive"))
      (node (ref "U12") (pin "1") (pinfunction "D1+_1") (pintype "passive"))
      (node (ref "U12") (pin "10") (pinfunction "NC_10") (pintype "passive"))
      (node (ref "U14") (pin "23") (pinfunction "OUT_D1-_23") (pintype "output"))
    )
    (net (code "66") (name "/TMDS_D0_P") (class "Default")
      (node (ref "J5") (pin "7") (pinfunction "D0+_7") (pintype "passive"))
      (node (ref "U12") (pin "2") (pinfunction "D1-_2") (pintype "passive"))
      (node (ref "U12") (pin "9") (pinfunction "NC_9") (pintype "passive"))
      (node (ref "U14") (pin "22") (pinfunction "OUT_D1+_22") (pintype "output"))
    )
    (net (code "67") (name "/TMDS_D1_N") (class "Default")
      (node (ref "J5") (pin "6") (pinfunction "D1-_6") (pintype "passive"))
      (node (ref "U12") (pin "4") (pinfunction "D2+_4") (pintype "passive"))
      (node (ref "U12") (pin "7") (pinfunction "NC_7") (pintype "passive"))
      (node (ref "U14") (pin "20") (pinfunction "OUT_D2-_20") (pintype "output"))
    )
    (net (code "68") (name "/TMDS_D1_P") (class "Default")
      (node (ref "J5") (pin "4") (pinfunction "D1+_4") (pintype "passive"))
      (node (ref "U12") (pin "5") (pinfunction "D2-_5") (pintype "passive"))
      (node (ref "U12") (pin "6") (pinfunction "NC_6") (pintype "passive"))
      (node (ref "U14") (pin "19") (pinfunction "OUT_D2+_19") (pintype "output"))
    )
    (net (code "69") (name "/TMDS_D2_N") (class "Default")
      (node (ref "J5") (pin "3") (pinfunction "D2-_3") (pintype "passive"))
      (node (ref "U11") (pin "5") (pinfunction "D2-_5") (pintype "passive"))
      (node (ref "U11") (pin "6") (pinfunction "NC_6") (pintype "passive"))
      (node (ref "U14") (pin "17") (pinfunction "OUT_D3-_17") (pintype "output"))
    )
    (net (code "70") (name "/TMDS_D2_P") (class "Default")
      (node (ref "J5") (pin "1") (pinfunction "D2+_1") (pintype "passive"))
      (node (ref "U11") (pin "4") (pinfunction "D2+_4") (pintype "passive"))
      (node (ref "U11") (pin "7") (pinfunction "NC_7") (pintype "passive"))
      (node (ref "U14") (pin "16") (pinfunction "OUT_D3+_16") (pintype "output"))
    )
    (net (code "71") (name "/TRD0_N") (class "Default")
      (node (ref "T1") (pin "12") (pinfunction "TD4-_12") (pintype "passive"))
    )
    (net (code "72") (name "/TRD0_P") (class "Default")
      (node (ref "T1") (pin "11") (pinfunction "TD4+_11") (pintype "passive"))
    )
    (net (code "73") (name "/TRD1_N") (class "Default")
      (node (ref "T1") (pin "6") (pinfunction "TD2-_6") (pintype "passive"))
    )
    (net (code "74") (name "/TRD1_P") (class "Default")
      (node (ref "T1") (pin "5") (pinfunction "TD2+_5") (pintype "passive"))
    )
    (net (code "75") (name "/TRD2_N") (class "Default")
      (node (ref "T1") (pin "9") (pinfunction "TD3-_9") (pintype "passive"))
    )
    (net (code "76") (name "/TRD2_P") (class "Default")
      (node (ref "T1") (pin "8") (pinfunction "TD3+_8") (pintype "passive"))
    )
    (net (code "77") (name "/TRD3_N") (class "Default")
      (node (ref "T1") (pin "3") (pinfunction "TD1-_3") (pintype "passive"))
    )
    (net (code "78") (name "/TRD3_P") (class "Default")
      (node (ref "T1") (pin "2") (pinfunction "TD1+_2") (pintype "passive"))
    )
    (net (code "79") (name "GND") (class "Default")
      (node (ref "BT1") (pin "2") (pinfunction "2_2") (pintype "passive"))
      (node (ref "C10") (pin "1") (pinfunction "1_1") (pintype "passive"))
      (node (ref "C11") (pin "1") (pinfunction "1_1") (pintype "passive"))
      (node (ref "C12") (pin "1") (pinfunction "1_1") (pintype "passive"))
      (node (ref "C13") (pin "1") (pinfunction "1_1") (pintype "passive"))
      (node (ref "C15") (pin "2") (pinfunction "2_2") (pintype "passive"))
      (node (ref "C16") (pin "1") (pinfunction "1_1") (pintype "passive"))
      (node (ref "C17") (pin "1") (pinfunction "1_1") (pintype "passive"))
      (node (ref "C18") (pin "1") (pinfunction "1_1") (pintype "passive"))
      (node (ref "C19") (pin "1") (pinfunction "1_1") (pintype "passive"))
      (node (ref "C28") (pin "1") (pinfunction "1_1") (pintype "passive"))
      (node (ref "C29") (pin "1") (pinfunction "1_1") (pintype "passive"))
      (node (ref "C8") (pin "1") (pinfunction "1_1") (pintype "passive"))
      (node (ref "C9") (pin "1") (pinfunction "1_1") (pintype "passive"))
      (node (ref "J2") (pin "1") (pinfunction "1_1") (pintype "passive"))
      (node (ref "J2") (pin "11") (pinfunction "11_11") (pintype "passive"))
      (node (ref "J2") (pin "12") (pinfunction "12_12") (pintype "passive"))
      (node (ref "J2") (pin "13") (pinfunction "13_13") (pintype "passive"))
      (node (ref "J2") (pin "17") (pinfunction "17_17") (pintype "passive"))
      (node (ref "J2") (pin "18") (pinfunction "18_18") (pintype "passive"))
      (node (ref "J2") (pin "19") (pinfunction "19_19") (pintype "passive"))
      (node (ref "J2") (pin "4") (pinfunction "4_4") (pintype "passive"))
      (node (ref "J2") (pin "7") (pinfunction "7_7") (pintype "passive"))
      (node (ref "J3") (pin "9") (pinfunction "9_9") (pintype "passive"))
      (node (ref "J5") (pin "11") (pinfunction "CK_SHIELD_11") (pintype "passive"))
      (node (ref "J5") (pin "17") (pinfunction "GND_17") (pintype "passive"))
      (node (ref "J5") (pin "2") (pinfunction "D2_SHIELD_2") (pintype "passive"))
      (node (ref "J5") (pin "5") (pinfunction "D1_SHIELD_5") (pintype "passive"))
      (node (ref "J5") (pin "8") (pinfunction "D0_SHIELD_8") (pintype "passive"))
      (node (ref "J5") (pin "MTG1") (pinfunction "MTG1_MTG1") (pintype "passive"))
      (node (ref "J5") (pin "MTG2") (pinfunction "MTG2_MTG2") (pintype "passive"))
      (node (ref "J5") (pin "MTG3") (pinfunction "MTG3_MTG3") (pintype "passive"))
      (node (ref "J5") (pin "MTG4") (pinfunction "MTG4_MTG4") (pintype "passive"))
      (node (ref "P2") (pin "2") (pinfunction "2_2") (pintype "passive"))
      (node (ref "Q1") (pin "2") (pinfunction "S_2") (pintype "passive"))
      (node (ref "Q2") (pin "2") (pinfunction "SOURCE_2") (pintype "passive"))
      (node (ref "Q3") (pin "2") (pinfunction "SOURCE_2") (pintype "passive"))
      (node (ref "R21") (pin "2") (pinfunction "2_2") (pintype "passive"))
      (node (ref "U10") (pin "1") (pinfunction "*1OE_1") (pintype "passive"))
      (node (ref "U10") (pin "10") (pinfunction "GND_10") (pintype "power_in"))
      (node (ref "U10") (pin "11") (pinfunction "2A1_11") (pintype "passive"))
      (node (ref "U10") (pin "19") (pinfunction "*2OE_19") (pintype "passive"))
      (node (ref "U11") (pin "3") (pinfunction "GND_3") (pintype "power_in"))
      (node (ref "U11") (pin "8") (pinfunction "GND_8") (pintype "power_in"))
      (node (ref "U12") (pin "3") (pinfunction "GND_3") (pintype "power_in"))
      (node (ref "U12") (pin "8") (pinfunction "GND_8") (pintype "power_in"))
      (node (ref "U14") (pin "1") (pinfunction "GND_1") (pintype "power_in"))
      (node (ref "U14") (pin "12") (pinfunction "GND_12") (pintype "power_in"))
      (node (ref "U14") (pin "18") (pinfunction "GND_18") (pintype "power_in"))
      (node (ref "U14") (pin "24") (pinfunction "GND_24") (pintype "power_in"))
      (node (ref "U14") (pin "25") (pinfunction "~{OE}_25") (pintype "passive"))
      (node (ref "U14") (pin "27") (pinfunction "GND_27") (pintype "power_in"))
      (node (ref "U14") (pin "31") (pinfunction "GND_31") (pintype "power_in"))
      (node (ref "U14") (pin "36") (pinfunction "GND_36") (pintype "power_in"))
      (node (ref "U14") (pin "37") (pinfunction "GND_37") (pintype "power_in"))
      (node (ref "U14") (pin "43") (pinfunction "GND_43") (pintype "power_in"))
      (node (ref "U14") (pin "49") (pinfunction "EP_49") (pintype "passive"))
      (node (ref "U14") (pin "5") (pinfunction "GND_5") (pintype "power_in"))
      (node (ref "U2") (pin "1") (pinfunction "1_1") (pintype "passive"))
      (node (ref "U3") (pin "1") (pinfunction "1_1") (pintype "passive"))
      (node (ref "U4") (pin "1") (pinfunction "1_1") (pintype "passive"))
      (node (ref "U5") (pin "1") (pinfunction "1_1") (pintype "passive"))
      (node (ref "U6") (pin "1") (pinfunction "1_1") (pintype "passive"))
      (node (ref "U7") (pin "1") (pinfunction "1_1") (pintype "passive"))
      (node (ref "U8") (pin "1") (pinfunction "1_1") (pintype "passive"))
      (node (ref "U9") (pin "1") (pinfunction "NC_1") (pintype "passive"))
      (node (ref "U9") (pin "3") (pinfunction "GND_3") (pintype "passive"))
    )
    (net (code "80") (name "Net-(BT1-Pad1)") (class "Default")
      (node (ref "BT1") (pin "1") (pinfunction "1_1") (pintype "passive"))
      (node (ref "U13") (pin "1") (pinfunction "1_1") (pintype "passive"))
    )
    (net (code "81") (name "Net-(C14-Pad2)") (class "Default")
      (node (ref "C14") (pin "2") (pinfunction "2_2") (pintype "passive"))
      (node (ref "R6") (pin "2") (pinfunction "2_2") (pintype "passive"))
      (node (ref "R7") (pin "2") (pinfunction "2_2") (pintype "passive"))
      (node (ref "R8") (pin "2") (pinfunction "2_2") (pintype "passive"))
      (node (ref "R9") (pin "2") (pinfunction "2_2") (pintype "passive"))
    )
    (net (code "82") (name "Net-(D3-K)") (class "Default")
      (node (ref "D3") (pin "2") (pinfunction "K_2") (pintype "passive"))
      (node (ref "R10") (pin "1") (pinfunction "1_1") (pintype "passive"))
    )
    (net (code "83") (name "Net-(D4-ANODE)") (class "Default")
      (node (ref "C28") (pin "2") (pinfunction "2_2") (pintype "passive"))
      (node (ref "C29") (pin "2") (pinfunction "2_2") (pintype "passive"))
      (node (ref "D4") (pin "2") (pinfunction "ANODE_2") (pintype "passive"))
      (node (ref "FB1") (pin "1") (pinfunction "1_1") (pintype "passive"))
    )
    (net (code "84") (name "Net-(F1-Pad1)") (class "Default")
      (node (ref "F1") (pin "1") (pinfunction "1_1") (pintype "passive"))
      (node (ref "J3") (pin "10") (pinfunction "10_10") (pintype "passive"))
    )
    (net (code "85") (name "Net-(F2-Pad1)") (class "Default")
      (node (ref "F2") (pin "1") (pinfunction "1_1") (pintype "passive"))
      (node (ref "FB1") (pin "2") (pinfunction "2_2") (pintype "passive"))
    )
    (net (code "86") (name "Net-(J5-HP_DET)") (class "Default")
      (node (ref "J5") (pin "19") (pinfunction "HP_DET_19") (pintype "passive"))
      (node (ref "Q3") (pin "1") (pinfunction "GATE_1") (pintype "passive"))
      (node (ref "R21") (pin "1") (pinfunction "1_1") (pintype "passive"))
    )
    (net (code "87") (name "Net-(LS1--V)") (class "Default")
      (node (ref "LS1") (pin "2") (pinfunction "-V_2") (pintype "passive"))
      (node (ref "R11") (pin "2") (pinfunction "2_2") (pintype "passive"))
    )
    (net (code "88") (name "Net-(Q1-D)") (class "Default")
      (node (ref "Q1") (pin "3") (pinfunction "D_3") (pintype "passive"))
      (node (ref "R11") (pin "1") (pinfunction "1_1") (pintype "passive"))
    )
    (net (code "89") (name "Net-(Q1-G)") (class "Default")
      (node (ref "Q1") (pin "1") (pinfunction "G_1") (pintype "passive"))
      (node (ref "R12") (pin "2") (pinfunction "2_2") (pintype "passive"))
    )
    (net (code "90") (name "Net-(Q2-DRAIN)") (class "Default")
      (node (ref "Q2") (pin "3") (pinfunction "DRAIN_3") (pintype "passive"))
      (node (ref "R22") (pin "2") (pinfunction "2_2") (pintype "passive"))
      (node (ref "U14") (pin "30") (pinfunction "HPD_SNK_30") (pintype "passive"))
    )
    (net (code "91") (name "Net-(Q2-GATE)") (class "Default")
      (node (ref "Q2") (pin "1") (pinfunction "GATE_1") (pintype "passive"))
      (node (ref "Q3") (pin "3") (pinfunction "DRAIN_3") (pintype "passive"))
      (node (ref "R23") (pin "2") (pinfunction "2_2") (pintype "passive"))
    )
    (net (code "92") (name "Net-(R15-Pad2)") (class "Default")
      (node (ref "R15") (pin "2") (pinfunction "2_2") (pintype "passive"))
      (node (ref "U13") (pin "3") (pinfunction "3_3") (pintype "passive"))
    )
    (net (code "93") (name "Net-(U9-Y)") (class "Default")
      (node (ref "R10") (pin "2") (pinfunction "2_2") (pintype "passive"))
      (node (ref "U9") (pin "4") (pinfunction "Y_4") (pintype "passive"))
    )
    (net (code "94") (name "Net-(U10-1Y1)") (class "Default")
      (node (ref "J3") (pin "1") (pinfunction "1_1") (pintype "passive"))
      (node (ref "U10") (pin "18") (pinfunction "1Y1_18") (pintype "passive"))
      (node (ref "U7") (pin "3") (pinfunction "3_3") (pintype "passive"))
    )
    (net (code "95") (name "Net-(U10-1Y2)") (class "Default")
      (node (ref "J3") (pin "3") (pinfunction "3_3") (pintype "passive"))
      (node (ref "U10") (pin "16") (pinfunction "1Y2_16") (pintype "passive"))
      (node (ref "U5") (pin "3") (pinfunction "3_3") (pintype "passive"))
    )
    (net (code "96") (name "Net-(U10-1Y3)") (class "Default")
      (node (ref "J3") (pin "5") (pinfunction "5_5") (pintype "passive"))
      (node (ref "U10") (pin "14") (pinfunction "1Y3_14") (pintype "passive"))
      (node (ref "U3") (pin "3") (pinfunction "3_3") (pintype "passive"))
    )
    (net (code "97") (name "Net-(U10-1Y4)") (class "Default")
      (node (ref "J3") (pin "7") (pinfunction "7_7") (pintype "passive"))
      (node (ref "U10") (pin "12") (pinfunction "1Y4_12") (pintype "passive"))
      (node (ref "U2") (pin "3") (pinfunction "3_3") (pintype "passive"))
    )
    (net (code "98") (name "Net-(U10-2A2)") (class "Default")
      (node (ref "J3") (pin "4") (pinfunction "4_4") (pintype "passive"))
      (node (ref "U10") (pin "13") (pinfunction "2A2_13") (pintype "passive"))
      (node (ref "U4") (pin "3") (pinfunction "3_3") (pintype "passive"))
    )
    (net (code "99") (name "Net-(U10-2A3)") (class "Default")
      (node (ref "J3") (pin "6") (pinfunction "6_6") (pintype "passive"))
      (node (ref "U10") (pin "15") (pinfunction "2A3_15") (pintype "passive"))
      (node (ref "U6") (pin "3") (pinfunction "3_3") (pintype "passive"))
    )
    (net (code "100") (name "Net-(U10-2A4)") (class "Default")
      (node (ref "J3") (pin "8") (pinfunction "8_8") (pintype "passive"))
      (node (ref "U10") (pin "17") (pinfunction "2A4_17") (pintype "passive"))
      (node (ref "U8") (pin "3") (pinfunction "3_3") (pintype "passive"))
    )
    (net (code "101") (name "Net-(U14-DDC_EN)") (class "Default")
      (node (ref "R18") (pin "1") (pinfunction "1_1") (pintype "passive"))
      (node (ref "U14") (pin "32") (pinfunction "DDC_EN_32") (pintype "passive"))
    )
    (net (code "102") (name "unconnected-(J2-Pad23)") (class "Default")
      (node (ref "J2") (pin "23") (pinfunction "23_23") (pintype "passive+no_connect"))
    )
    (net (code "103") (name "unconnected-(J3-Pad2)") (class "Default")
      (node (ref "J3") (pin "2") (pinfunction "2_2") (pintype "passive+no_connect"))
    )
    (net (code "104") (name "unconnected-(J4-HOLE1-Pad15)") (class "Default")
      (node (ref "J4") (pin "15") (pinfunction "HOLE1_15") (pintype "passive+no_connect"))
    )
    (net (code "105") (name "unconnected-(J4-HOLE2-Pad16)") (class "Default")
      (node (ref "J4") (pin "16") (pinfunction "HOLE2_16") (pintype "passive+no_connect"))
    )
    (net (code "106") (name "unconnected-(J5-CE_REMOTE-Pad13)") (class "Default")
      (node (ref "J5") (pin "13") (pinfunction "CE_REMOTE_13") (pintype "passive+no_connect"))
    )
    (net (code "107") (name "unconnected-(J5-NC.14-Pad14)") (class "Default")
      (node (ref "J5") (pin "14") (pinfunction "NC.14_14") (pintype "passive+no_connect"))
    )
    (net (code "108") (name "unconnected-(U10-2Y1-Pad9)") (class "Default")
      (node (ref "U10") (pin "9") (pinfunction "2Y1_9") (pintype "passive+no_connect"))
    )
    (net (code "109") (name "unconnected-(U13-Pad2)") (class "Default")
      (node (ref "U13") (pin "2") (pinfunction "2_2") (pintype "passive+no_connect"))
    )
    (net (code "110") (name "unconnected-(U14-N.C.-Pad3)") (class "Default")
      (node (ref "U14") (pin "3") (pinfunction "N.C._3") (pintype "passive+no_connect"))
    )
    (net (code "111") (name "unconnected-(U14-N.C.-Pad4)") (class "Default")
      (node (ref "U14") (pin "4") (pinfunction "N.C._4") (pintype "passive+no_connect"))
    )
    (net (code "112") (name "unconnected-(U14-N.C.-Pad6)") (class "Default")
      (node (ref "U14") (pin "6") (pinfunction "N.C._6") (pintype "passive+no_connect"))
    )
    (net (code "113") (name "unconnected-(U14-N.C.-Pad10)") (class "Default")
      (node (ref "U14") (pin "10") (pinfunction "N.C._10") (pintype "passive+no_connect"))
    )
    (net (code "114") (name "unconnected-(U14-N.C.-Pad34)") (class "Default")
      (node (ref "U14") (pin "34") (pinfunction "N.C._34") (pintype "passive+no_connect"))
    )
    (net (code "115") (name "unconnected-(U14-N.C.-Pad35)") (class "Default")
      (node (ref "U14") (pin "35") (pinfunction "N.C._35") (pintype "passive+no_connect"))
    )
  )
)
